# CCP_MCU_IO_CN12.net
KiCad netlist of a schematic drawn in Altium Designer
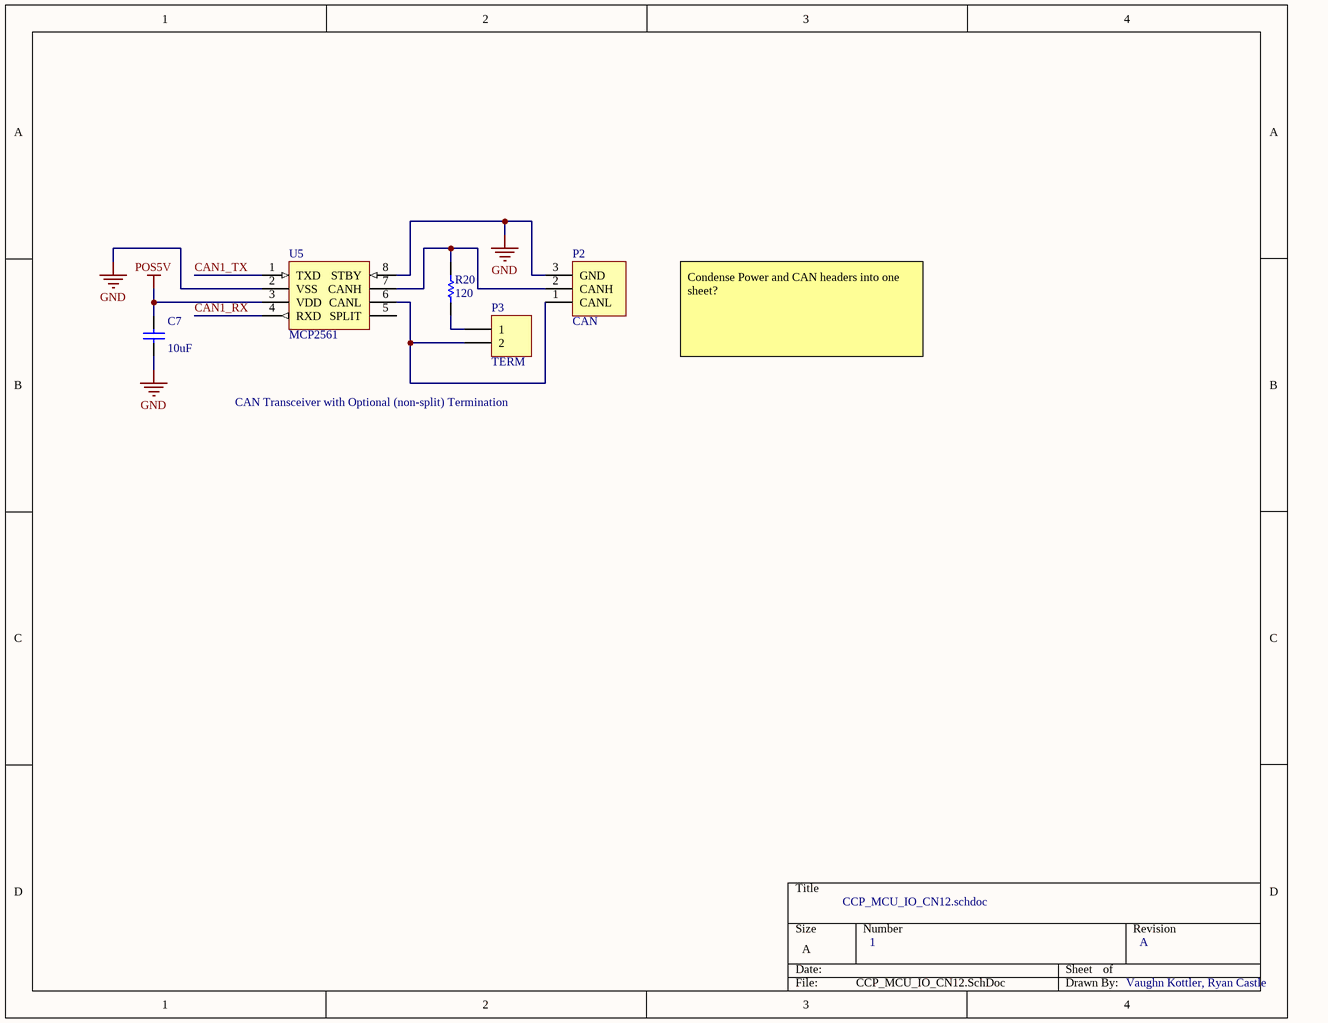
[diagram p0: CCP_MCU_IO_CN12.SchDoc]

(export (version "E")
  (design (tool "Eeschema 10.0.6"))
  (components
    (comp (ref "C7")
      (value "10uF")
      (footprint "C1206")
      (description "Capacitor")
      (fields (field (name "Comment") "Cap") (field (name "PUBLISHER") "Altium Limited"))
      (libsource (lib "Miscellaneous Devices") (part "Cap"))
    )
    (comp (ref "P2") (value "CAN") (footprint "3POS TERM BLOCK") (libsource (lib "connector") (part "CAN")))
    (comp (ref "P3")
      (value "TERM")
      (footprint "HDR1X2")
      (description "Header, 2-Pin")
      (fields (field (name "PUBLISHER") "Altium Limited"))
      (libsource (lib "Miscellaneous Connectors") (part "Header 2"))
    )
    (comp (ref "R20")
      (value "120")
      (footprint "6-0805_M")
      (description "Resistor")
      (fields (field (name "Comment") "Res1") (field (name "PUBLISHER") "Altium Limited"))
      (libsource (lib "Miscellaneous Devices") (part "Res1"))
    )
    (comp (ref "U5")
      (value "MCP2561")
      (footprint "SO8_L")
      (description "CAN Transciever")
      (libsource (lib "ic") (part "MCP2561"))
    )
  )
  (nets
    (net (code "1") (name "/CAN1_RX") (class "Default")
      (node (ref "U5") (pin "4") (pinfunction "RXD_4") (pintype "output"))
    )
    (net (code "2") (name "/CAN1_TX") (class "Default")
      (node (ref "U5") (pin "1") (pinfunction "TXD_1") (pintype "input"))
    )
    (net (code "3") (name "GND") (class "Default")
      (node (ref "C7") (pin "1") (pinfunction "1_1") (pintype "passive"))
      (node (ref "P2") (pin "3") (pinfunction "GND_3") (pintype "passive"))
      (node (ref "U5") (pin "2") (pinfunction "VSS_2") (pintype "power_in"))
      (node (ref "U5") (pin "8") (pinfunction "STBY_8") (pintype "input"))
    )
    (net (code "4") (name "Net-(P2-CANH)") (class "Default")
      (node (ref "P2") (pin "2") (pinfunction "CANH_2") (pintype "passive"))
      (node (ref "R20") (pin "2") (pinfunction "2_2") (pintype "passive"))
      (node (ref "U5") (pin "7") (pinfunction "CANH_7") (pintype "passive"))
    )
    (net (code "5") (name "Net-(P2-CANL)") (class "Default")
      (node (ref "P2") (pin "1") (pinfunction "CANL_1") (pintype "passive"))
      (node (ref "P3") (pin "2") (pinfunction "2_2") (pintype "passive"))
      (node (ref "U5") (pin "6") (pinfunction "CANL_6") (pintype "passive"))
    )
    (net (code "6") (name "Net-(P3-Pad1)") (class "Default")
      (node (ref "P3") (pin "1") (pinfunction "1_1") (pintype "passive"))
      (node (ref "R20") (pin "1") (pinfunction "1_1") (pintype "passive"))
    )
    (net (code "7") (name "POS5V") (class "Default")
      (node (ref "C7") (pin "2") (pinfunction "2_2") (pintype "passive"))
      (node (ref "U5") (pin "3") (pinfunction "VDD_3") (pintype "passive"))
    )
    (net (code "8") (name "unconnected-(U5-SPLIT-Pad5)") (class "Default")
      (node (ref "U5") (pin "5") (pinfunction "SPLIT_5") (pintype "passive"))
    )
  )
)
